# LED_Driver.net
KiCad netlist of a schematic drawn in EAGLE
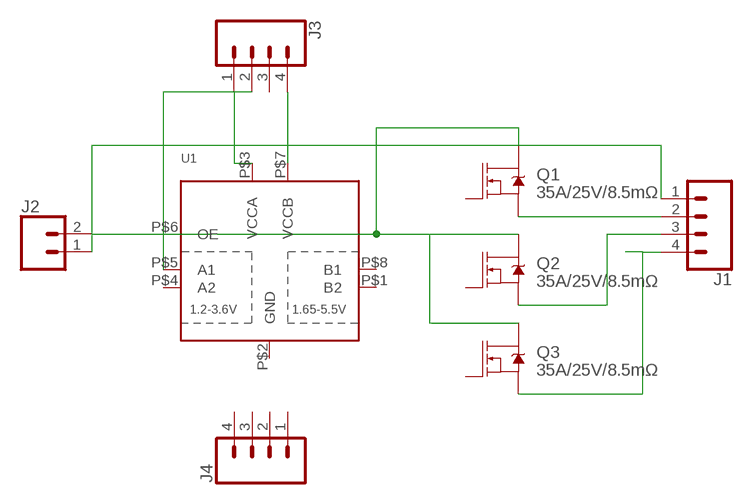
[diagram p0: schematic, sheet 1]

(export (version "E")
  (design (tool "Eeschema 10.0.6"))
  (components
    (comp (ref "J1")
      (value "CONN_04SCREW")
      (footprint "eagle-import:SCREWTERMINAL-3.5MM-4")
      (libsource (lib "eagle-import") (part "CONN_04SCREW"))
    )
    (comp (ref "J2")
      (value "CONN_023.5MM")
      (footprint "eagle-import:SCREWTERMINAL-3.5MM-2")
      (libsource (lib "eagle-import") (part "CONN_023.5MM"))
    )
    (comp (ref "J3")
      (value "CONN_04JST-PTH")
      (footprint "eagle-import:JST-4-PTH")
      (libsource (lib "eagle-import") (part "CONN_04JST-PTH"))
    )
    (comp (ref "J4")
      (value "CONN_04JST-PTH")
      (footprint "eagle-import:JST-4-PTH")
      (libsource (lib "eagle-import") (part "CONN_04JST-PTH"))
    )
    (comp (ref "Q1")
      (value "35A/25V/8.5mΩ")
      (footprint "eagle-import:DPAK")
      (libsource (lib "eagle-import") (part "MOSFET-NCH-FDD8780"))
    )
    (comp (ref "Q2")
      (value "35A/25V/8.5mΩ")
      (footprint "eagle-import:DPAK")
      (libsource (lib "eagle-import") (part "MOSFET-NCH-FDD8780"))
    )
    (comp (ref "Q3")
      (value "35A/25V/8.5mΩ")
      (footprint "eagle-import:DPAK")
      (libsource (lib "eagle-import") (part "MOSFET-NCH-FDD8780"))
    )
    (comp (ref "U1")
      (value "TXS0102")
      (footprint "eagle-import:VFSOP-8")
      (libsource (lib "eagle-import") (part "TXS0102"))
    )
  )
  (nets
    (net (code "1") (name "Net-(J1-Pad1)") (class "Default")
      (node (ref "J1") (pin "1") (pinfunction "1_1") (pintype "passive"))
      (node (ref "J2") (pin "1") (pinfunction "1_1") (pintype "passive"))
    )
    (net (code "2") (name "Net-(Q1-D)") (class "Default")
      (node (ref "J2") (pin "2") (pinfunction "2_2") (pintype "passive"))
      (node (ref "Q1") (pin "4") (pinfunction "D_4") (pintype "bidirectional"))
      (node (ref "Q2") (pin "4") (pinfunction "D_4") (pintype "bidirectional"))
      (node (ref "Q3") (pin "4") (pinfunction "D_4") (pintype "bidirectional"))
    )
    (net (code "3") (name "Net-(Q1-S)") (class "Default")
      (node (ref "J1") (pin "2") (pinfunction "2_2") (pintype "passive"))
      (node (ref "Q1") (pin "3") (pinfunction "S_3") (pintype "bidirectional"))
    )
    (net (code "4") (name "Net-(Q2-S)") (class "Default")
      (node (ref "J1") (pin "3") (pinfunction "3_3") (pintype "passive"))
      (node (ref "Q2") (pin "3") (pinfunction "S_3") (pintype "bidirectional"))
    )
    (net (code "5") (name "Net-(Q3-S)") (class "Default")
      (node (ref "J1") (pin "4") (pinfunction "4_4") (pintype "passive"))
      (node (ref "Q3") (pin "3") (pinfunction "S_3") (pintype "bidirectional"))
    )
    (net (code "6") (name "Net-(U1-A1)") (class "Default")
      (node (ref "J3") (pin "2") (pinfunction "2_2") (pintype "passive"))
      (node (ref "U1") (pin "P$5") (pinfunction "A1_P$5") (pintype "bidirectional"))
    )
    (net (code "7") (name "Net-(U1-VCCA)") (class "Default")
      (node (ref "J3") (pin "1") (pinfunction "1_1") (pintype "passive"))
      (node (ref "U1") (pin "P$3") (pinfunction "VCCA_P$3") (pintype "bidirectional"))
    )
    (net (code "8") (name "Net-(U1-VCCB)") (class "Default")
      (node (ref "J3") (pin "4") (pinfunction "4_4") (pintype "passive"))
      (node (ref "U1") (pin "P$7") (pinfunction "VCCB_P$7") (pintype "bidirectional"))
    )
    (net (code "9") (name "unconnected-(J3-Pad3)") (class "Default")
      (node (ref "J3") (pin "3") (pinfunction "3_3") (pintype "passive"))
    )
    (net (code "10") (name "unconnected-(J4-Pad1)") (class "Default")
      (node (ref "J4") (pin "1") (pinfunction "1_1") (pintype "passive"))
    )
    (net (code "11") (name "unconnected-(J4-Pad2)") (class "Default")
      (node (ref "J4") (pin "2") (pinfunction "2_2") (pintype "passive"))
    )
    (net (code "12") (name "unconnected-(J4-Pad3)") (class "Default")
      (node (ref "J4") (pin "3") (pinfunction "3_3") (pintype "passive"))
    )
    (net (code "13") (name "unconnected-(J4-Pad4)") (class "Default")
      (node (ref "J4") (pin "4") (pinfunction "4_4") (pintype "passive"))
    )
    (net (code "14") (name "unconnected-(Q1-G-Pad1)") (class "Default")
      (node (ref "Q1") (pin "1") (pinfunction "G_1") (pintype "bidirectional"))
    )
    (net (code "15") (name "unconnected-(Q2-G-Pad1)") (class "Default")
      (node (ref "Q2") (pin "1") (pinfunction "G_1") (pintype "bidirectional"))
    )
    (net (code "16") (name "unconnected-(Q3-G-Pad1)") (class "Default")
      (node (ref "Q3") (pin "1") (pinfunction "G_1") (pintype "bidirectional"))
    )
    (net (code "17") (name "unconnected-(U1-A2-PadP$4)") (class "Default")
      (node (ref "U1") (pin "P$4") (pinfunction "A2_P$4") (pintype "bidirectional"))
    )
    (net (code "18") (name "unconnected-(U1-B1-PadP$8)") (class "Default")
      (node (ref "U1") (pin "P$8") (pinfunction "B1_P$8") (pintype "bidirectional"))
    )
    (net (code "19") (name "unconnected-(U1-B2-PadP$1)") (class "Default")
      (node (ref "U1") (pin "P$1") (pinfunction "B2_P$1") (pintype "bidirectional"))
    )
    (net (code "20") (name "unconnected-(U1-GND-PadP$2)") (class "Default")
      (node (ref "U1") (pin "P$2") (pinfunction "GND_P$2") (pintype "bidirectional"))
    )
    (net (code "21") (name "unconnected-(U1-OE-PadP$6)") (class "Default")
      (node (ref "U1") (pin "P$6") (pinfunction "OE_P$6") (pintype "bidirectional"))
    )
  )
)
